# cansat.net
KiCad netlist of a schematic drawn in EAGLE
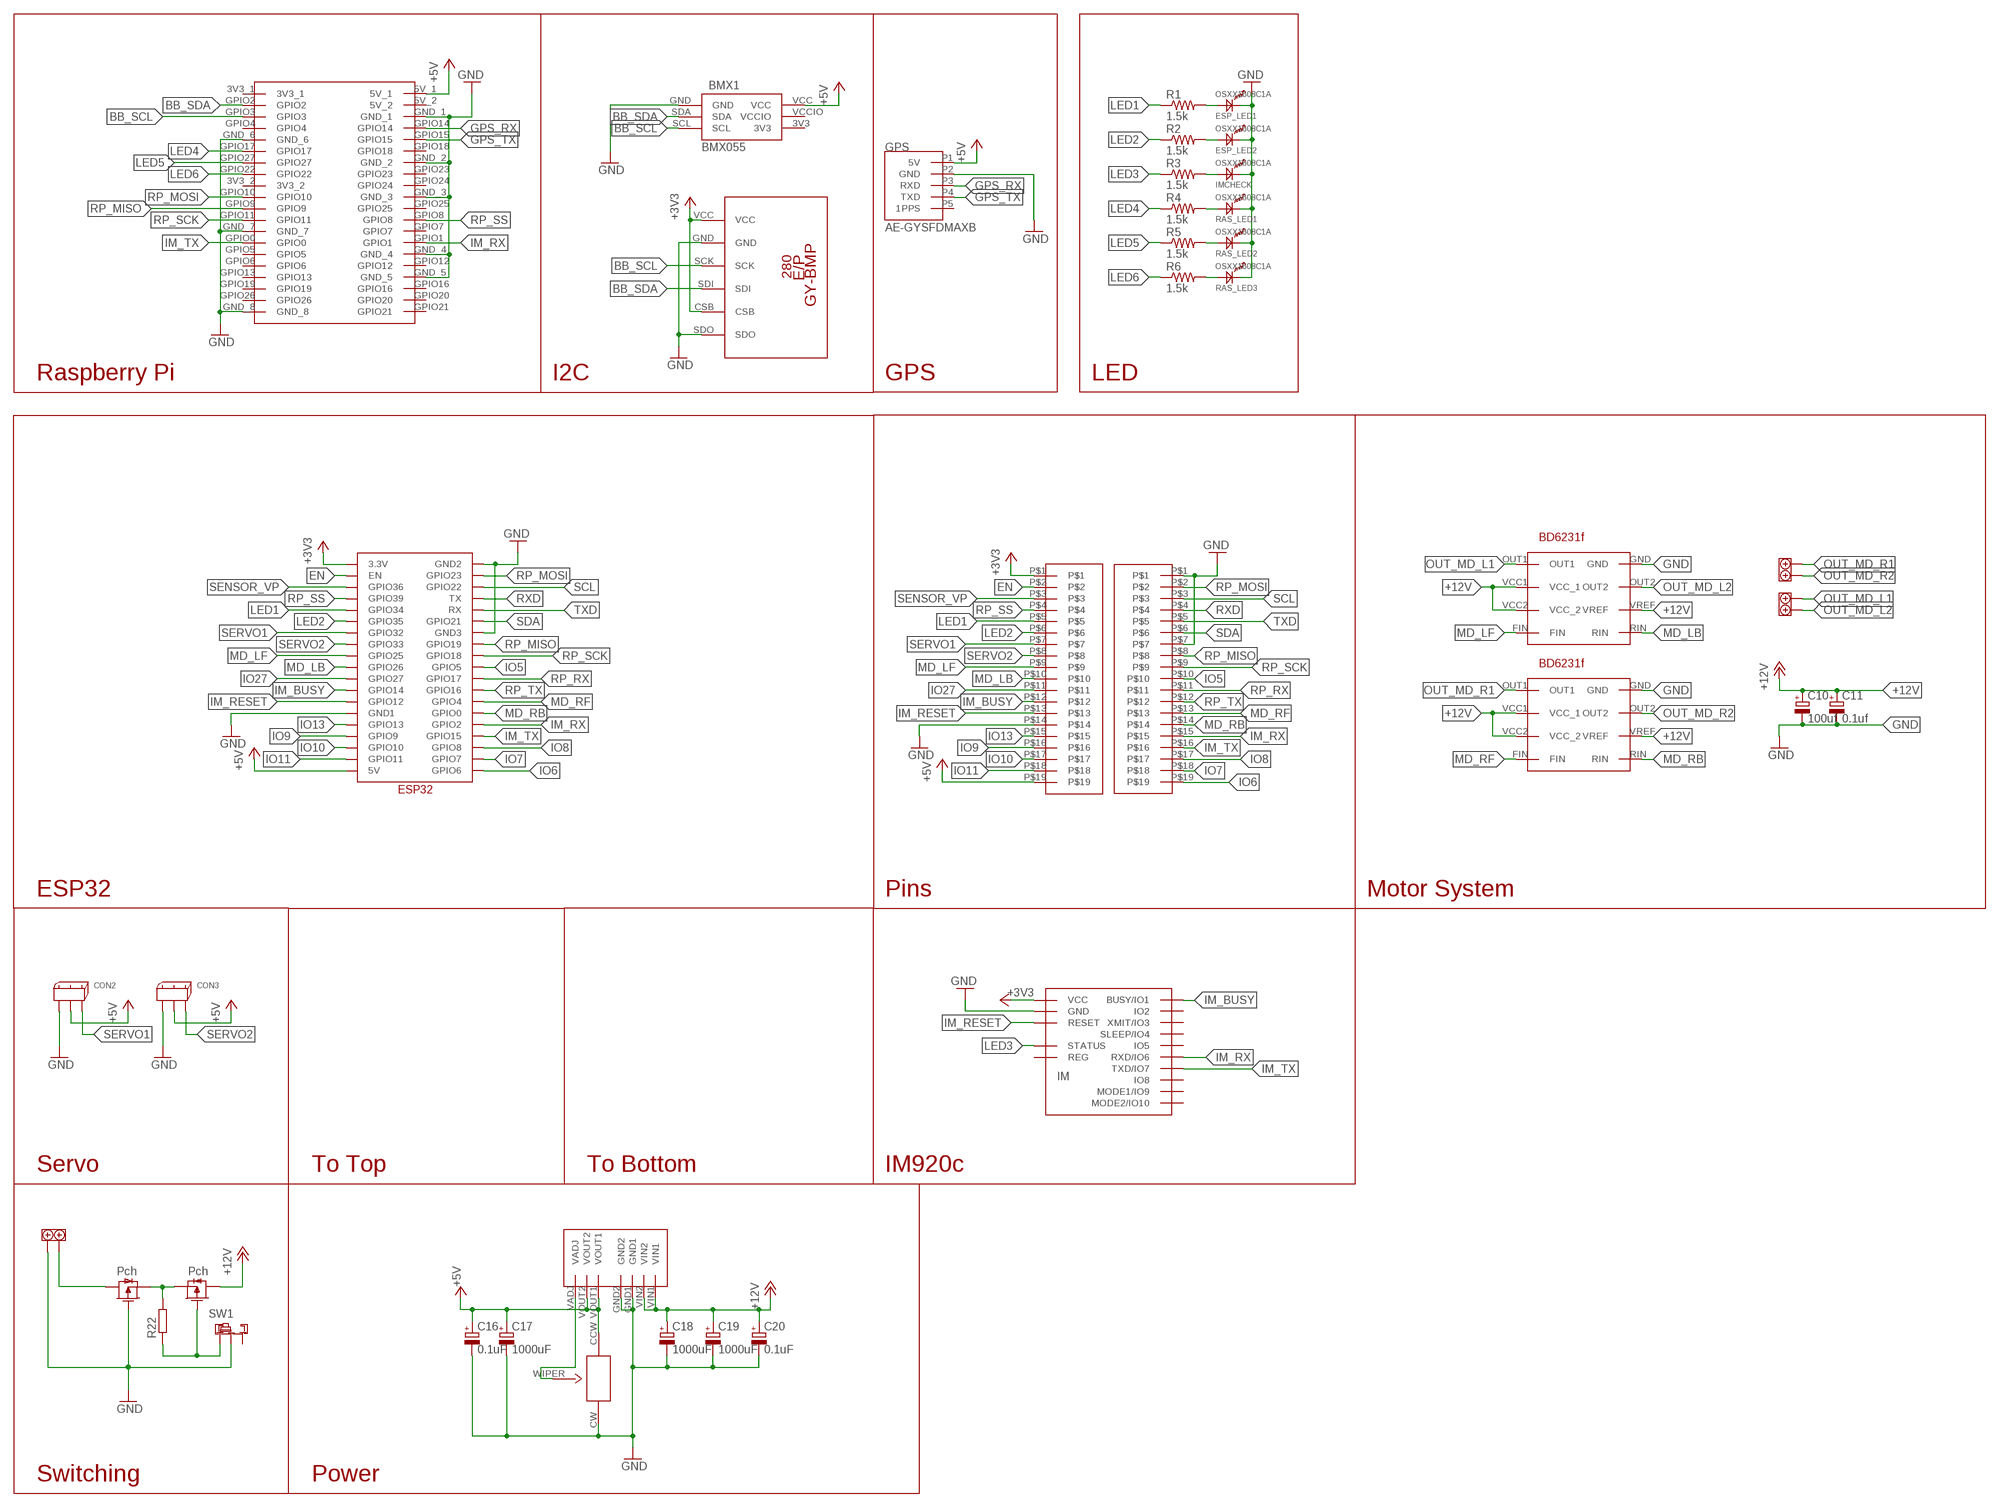
[diagram p0: schematic, sheet 1]

(export (version "E")
  (design (tool "Eeschema 10.0.6"))
  (components
    (comp (ref "100KR1")
      (value "100kR")
      (footprint "eagle-import:3362P")
      (libsource (lib "eagle-import") (part "3362P"))
    )
    (comp (ref "BMX1")
      (value "BMX055")
      (footprint "eagle-import:BMX055")
      (libsource (lib "eagle-import") (part "BMX055"))
    )
    (comp (ref "C10")
      (value "100uf")
      (footprint "eagle-import:E2,5-7")
      (libsource (lib "eagle-import") (part "CPOL-EUE2.5-7"))
    )
    (comp (ref "C11")
      (value "0.1uf")
      (footprint "eagle-import:E2,5-7")
      (libsource (lib "eagle-import") (part "CPOL-EUE2.5-7"))
    )
    (comp (ref "C16")
      (value "0.1uF")
      (footprint "eagle-import:E2,5-7")
      (libsource (lib "eagle-import") (part "CPOL-EUE2.5-7"))
    )
    (comp (ref "C17")
      (value "1000uF")
      (footprint "eagle-import:E5-10,5")
      (libsource (lib "eagle-import") (part "CPOL-EUE5-10.5"))
    )
    (comp (ref "C18")
      (value "1000uF")
      (footprint "eagle-import:E5-10,5")
      (libsource (lib "eagle-import") (part "CPOL-EUE5-10.5"))
    )
    (comp (ref "C19")
      (value "1000uF")
      (footprint "eagle-import:E5-10,5")
      (libsource (lib "eagle-import") (part "CPOL-EUE5-10.5"))
    )
    (comp (ref "C20")
      (value "0.1uF")
      (footprint "eagle-import:E2,5-7")
      (libsource (lib "eagle-import") (part "CPOL-EUE2.5-7"))
    )
    (comp (ref "CON2")
      (value "2.5_MINI-SPOX_3PIN")
      (footprint "eagle-import:2.5_MINI-SPOX_3PIN")
      (libsource (lib "eagle-import") (part "2.5_MINI-SPOX_3PIN"))
    )
    (comp (ref "CON3")
      (value "2.5_MINI-SPOX_3PIN")
      (footprint "eagle-import:2.5_MINI-SPOX_3PIN")
      (libsource (lib "eagle-import") (part "2.5_MINI-SPOX_3PIN"))
    )
    (comp (ref "ESP_LED1")
      (value "OSXX1608C1A")
      (footprint "eagle-import:OSXX1608C1A")
      (libsource (lib "eagle-import") (part "OSXX1608C1A"))
    )
    (comp (ref "ESP_LED2")
      (value "OSXX1608C1A")
      (footprint "eagle-import:OSXX1608C1A")
      (libsource (lib "eagle-import") (part "OSXX1608C1A"))
    )
    (comp (ref "GPS")
      (value "AE-GYSFDMAXB")
      (footprint "eagle-import:AE-GYSFDMAXB")
      (libsource (lib "eagle-import") (part "AE-GYSFDMAXB"))
    )
    (comp (ref "IM")
      (value "IM920C")
      (footprint "eagle-import:IM920C")
      (libsource (lib "eagle-import") (part "IM920C"))
    )
    (comp (ref "IMCHECK")
      (value "OSXX1608C1A")
      (footprint "eagle-import:OSXX1608C1A")
      (libsource (lib "eagle-import") (part "OSXX1608C1A"))
    )
    (comp (ref "MD_L")
      (value "BD6231F")
      (footprint "eagle-import:BD6231F")
      (libsource (lib "eagle-import") (part "BD6231F"))
    )
    (comp (ref "MD_R")
      (value "BD6231F")
      (footprint "eagle-import:BD6231F")
      (libsource (lib "eagle-import") (part "BD6231F"))
    )
    (comp (ref "PIN_L")
      (value "19_2.54")
      (footprint "eagle-import:19_2.54")
      (libsource (lib "eagle-import") (part "19_2.54"))
    )
    (comp (ref "PIN_R")
      (value "19_2.54")
      (footprint "eagle-import:19_2.54")
      (libsource (lib "eagle-import") (part "19_2.54"))
    )
    (comp (ref "R1")
      (value "1.5k")
      (footprint "eagle-import:R0603")
      (libsource (lib "eagle-import") (part "R-US_R0603"))
    )
    (comp (ref "R2")
      (value "1.5k")
      (footprint "eagle-import:R0603")
      (libsource (lib "eagle-import") (part "R-US_R0603"))
    )
    (comp (ref "R3")
      (value "1.5k")
      (footprint "eagle-import:R0603")
      (libsource (lib "eagle-import") (part "R-US_R0603"))
    )
    (comp (ref "R4")
      (value "1.5k")
      (footprint "eagle-import:R0603")
      (libsource (lib "eagle-import") (part "R-US_R0603"))
    )
    (comp (ref "R5")
      (value "1.5k")
      (footprint "eagle-import:R0603")
      (libsource (lib "eagle-import") (part "R-US_R0603"))
    )
    (comp (ref "R6")
      (value "1.5k")
      (footprint "eagle-import:R0603")
      (libsource (lib "eagle-import") (part "R-US_R0603"))
    )
    (comp (ref "R22")
      (value "R-EU_0207/10")
      (footprint "eagle-import:0207_10")
      (libsource (lib "eagle-import") (part "R-EU_0207/10"))
    )
    (comp (ref "RASPBERRYPI_4B")
      (value "RASPBERRYPI4B")
      (footprint "eagle-import:RASPBERRYPI4B")
      (libsource (lib "eagle-import") (part "RASPBERRYPI4B"))
    )
    (comp (ref "RAS_LED1")
      (value "OSXX1608C1A")
      (footprint "eagle-import:OSXX1608C1A")
      (libsource (lib "eagle-import") (part "OSXX1608C1A"))
    )
    (comp (ref "RAS_LED2")
      (value "OSXX1608C1A")
      (footprint "eagle-import:OSXX1608C1A")
      (libsource (lib "eagle-import") (part "OSXX1608C1A"))
    )
    (comp (ref "RAS_LED3")
      (value "OSXX1608C1A")
      (footprint "eagle-import:OSXX1608C1A")
      (libsource (lib "eagle-import") (part "OSXX1608C1A"))
    )
    (comp (ref "SW1")
      (value "SRIDE_SWITCH")
      (footprint "eagle-import:SRIDE_SWITCH")
      (libsource (lib "eagle-import") (part "SRIDE_SWITCH"))
    )
    (comp (ref "TM1")
      (value "TERMINAL_SLOPED_2PIN")
      (footprint "eagle-import:TERMINAL_SLOPED_2PIN")
      (libsource (lib "eagle-import") (part "TERMINAL_SLOPED_2PIN"))
    )
    (comp (ref "TM2")
      (value "TERMINAL_SLOPED_2PIN")
      (footprint "eagle-import:TERMINAL_SLOPED_2PIN")
      (libsource (lib "eagle-import") (part "TERMINAL_SLOPED_2PIN"))
    )
    (comp (ref "TM3")
      (value "TERMINAL_SLOPED_2PIN")
      (footprint "eagle-import:TERMINAL_SLOPED_2PIN")
      (libsource (lib "eagle-import") (part "TERMINAL_SLOPED_2PIN"))
    )
    (comp (ref "U$2")
      (value "ESP32")
      (footprint "eagle-import:ESP32")
      (libsource (lib "eagle-import") (part "ESP32"))
    )
    (comp (ref "U$7")
      (value "2SJ681-PCH")
      (footprint "eagle-import:2SJ681")
      (libsource (lib "eagle-import") (part "2SJ681-PCH"))
    )
    (comp (ref "U$8")
      (value "5V3A_KIC-053")
      (footprint "eagle-import:5V3A_KIC-053")
      (libsource (lib "eagle-import") (part "5V3A_KIC-053"))
    )
    (comp (ref "U$9")
      (value "GY-BPM280")
      (footprint "eagle-import:GY-BMP280-FOOTPRINT")
      (libsource (lib "eagle-import") (part "GY-BPM280"))
    )
    (comp (ref "U$10")
      (value "2SJ681-PCH")
      (footprint "eagle-import:2SJ681")
      (libsource (lib "eagle-import") (part "2SJ681-PCH"))
    )
  )
  (nets
    (net (code "1") (name "+3V3") (class "Default")
      (node (ref "IM") (pin "$P17") (pinfunction "VCC_$P17") (pintype "bidirectional"))
      (node (ref "PIN_L") (pin "P$1") (pinfunction "P$1_P$1") (pintype "bidirectional"))
      (node (ref "U$2") (pin "3.3V") (pinfunction "3.3V_3.3V") (pintype "bidirectional"))
      (node (ref "U$9") (pin "CSB") (pinfunction "CSB_CSB") (pintype "bidirectional"))
      (node (ref "U$9") (pin "VCC") (pinfunction "VCC_VCC") (pintype "bidirectional"))
    )
    (net (code "2") (name "+5V") (class "Default")
      (node (ref "100KR1") (pin "CCW") (pinfunction "CCW_CCW") (pintype "bidirectional"))
      (node (ref "BMX1") (pin "VCC") (pinfunction "VCC_VCC") (pintype "power_in"))
      (node (ref "C16") (pin "+") (pinfunction "+_+") (pintype "passive"))
      (node (ref "C17") (pin "+") (pinfunction "+_+") (pintype "passive"))
      (node (ref "CON2") (pin "2") (pinfunction "2_2") (pintype "bidirectional"))
      (node (ref "CON3") (pin "2") (pinfunction "2_2") (pintype "bidirectional"))
      (node (ref "GPS") (pin "P1") (pinfunction "5V_P1") (pintype "bidirectional"))
      (node (ref "PIN_L") (pin "P$19") (pinfunction "P$19_P$19") (pintype "bidirectional"))
      (node (ref "RASPBERRYPI_4B") (pin "5V_1") (pinfunction "5V_1_5V_1") (pintype "bidirectional"))
      (node (ref "U$2") (pin "5V") (pinfunction "5V_5V") (pintype "bidirectional"))
      (node (ref "U$8") (pin "VOUT1") (pinfunction "VOUT1_VOUT1") (pintype "bidirectional"))
      (node (ref "U$8") (pin "VOUT2") (pinfunction "VOUT2_VOUT2") (pintype "bidirectional"))
    )
    (net (code "3") (name "+12V") (class "Default")
      (node (ref "C10") (pin "+") (pinfunction "+_+") (pintype "passive"))
      (node (ref "C11") (pin "+") (pinfunction "+_+") (pintype "passive"))
      (node (ref "C18") (pin "+") (pinfunction "+_+") (pintype "passive"))
      (node (ref "C19") (pin "+") (pinfunction "+_+") (pintype "passive"))
      (node (ref "C20") (pin "+") (pinfunction "+_+") (pintype "passive"))
      (node (ref "MD_L") (pin "VCC1") (pinfunction "VCC_1_VCC1") (pintype "bidirectional"))
      (node (ref "MD_L") (pin "VCC2") (pinfunction "VCC_2_VCC2") (pintype "bidirectional"))
      (node (ref "MD_L") (pin "VREF") (pinfunction "VREF_VREF") (pintype "bidirectional"))
      (node (ref "MD_R") (pin "VCC1") (pinfunction "VCC_1_VCC1") (pintype "bidirectional"))
      (node (ref "MD_R") (pin "VCC2") (pinfunction "VCC_2_VCC2") (pintype "bidirectional"))
      (node (ref "MD_R") (pin "VREF") (pinfunction "VREF_VREF") (pintype "bidirectional"))
      (node (ref "U$10") (pin "DRAIN") (pinfunction "DRAIN_DRAIN") (pintype "bidirectional"))
      (node (ref "U$8") (pin "VIN1") (pinfunction "VIN1_VIN1") (pintype "bidirectional"))
      (node (ref "U$8") (pin "VIN2") (pinfunction "VIN2_VIN2") (pintype "bidirectional"))
    )
    (net (code "4") (name "/3V3") (class "Default")
      (node (ref "BMX1") (pin "3V3") (pinfunction "3V3_3V3") (pintype "power_in"))
    )
    (net (code "5") (name "/VCCIO") (class "Default")
      (node (ref "BMX1") (pin "VCCIO") (pinfunction "VCCIO_VCCIO") (pintype "power_in"))
    )
    (net (code "6") (name "BB_SCL") (class "Default")
      (node (ref "BMX1") (pin "SCL") (pinfunction "SCL_SCL") (pintype "bidirectional"))
      (node (ref "RASPBERRYPI_4B") (pin "GPIO3") (pinfunction "GPIO3_GPIO3") (pintype "bidirectional"))
      (node (ref "U$9") (pin "SCK") (pinfunction "SCK_SCK") (pintype "bidirectional"))
    )
    (net (code "7") (name "BB_SDA") (class "Default")
      (node (ref "BMX1") (pin "SDA") (pinfunction "SDA_SDA") (pintype "bidirectional"))
      (node (ref "RASPBERRYPI_4B") (pin "GPIO2") (pinfunction "GPIO2_GPIO2") (pintype "bidirectional"))
      (node (ref "U$9") (pin "SDI") (pinfunction "SDI_SDI") (pintype "bidirectional"))
    )
    (net (code "8") (name "EN") (class "Default")
      (node (ref "PIN_L") (pin "P$2") (pinfunction "P$2_P$2") (pintype "bidirectional"))
      (node (ref "U$2") (pin "EN") (pinfunction "EN_EN") (pintype "bidirectional"))
    )
    (net (code "9") (name "GND") (class "Default")
      (node (ref "100KR1") (pin "CW") (pinfunction "CW_CW") (pintype "bidirectional"))
      (node (ref "BMX1") (pin "GND") (pinfunction "GND_GND") (pintype "power_in"))
      (node (ref "C10") (pin "-") (pinfunction "-_-") (pintype "passive"))
      (node (ref "C11") (pin "-") (pinfunction "-_-") (pintype "passive"))
      (node (ref "C16") (pin "-") (pinfunction "-_-") (pintype "passive"))
      (node (ref "C17") (pin "-") (pinfunction "-_-") (pintype "passive"))
      (node (ref "C18") (pin "-") (pinfunction "-_-") (pintype "passive"))
      (node (ref "C19") (pin "-") (pinfunction "-_-") (pintype "passive"))
      (node (ref "C20") (pin "-") (pinfunction "-_-") (pintype "passive"))
      (node (ref "CON2") (pin "1") (pinfunction "1_1") (pintype "bidirectional"))
      (node (ref "CON3") (pin "1") (pinfunction "1_1") (pintype "bidirectional"))
      (node (ref "ESP_LED1") (pin "CT") (pinfunction "CT_CT") (pintype "bidirectional"))
      (node (ref "ESP_LED2") (pin "CT") (pinfunction "CT_CT") (pintype "bidirectional"))
      (node (ref "GPS") (pin "P2") (pinfunction "GND_P2") (pintype "bidirectional"))
      (node (ref "IM") (pin "$P18") (pinfunction "GND_$P18") (pintype "bidirectional"))
      (node (ref "IMCHECK") (pin "CT") (pinfunction "CT_CT") (pintype "bidirectional"))
      (node (ref "MD_L") (pin "GND") (pinfunction "GND_GND") (pintype "bidirectional"))
      (node (ref "MD_R") (pin "GND") (pinfunction "GND_GND") (pintype "bidirectional"))
      (node (ref "PIN_L") (pin "P$14") (pinfunction "P$14_P$14") (pintype "bidirectional"))
      (node (ref "PIN_R") (pin "P$1") (pinfunction "P$1_P$1") (pintype "bidirectional"))
      (node (ref "PIN_R") (pin "P$7") (pinfunction "P$7_P$7") (pintype "bidirectional"))
      (node (ref "RASPBERRYPI_4B") (pin "GND_1") (pinfunction "GND_1_GND_1") (pintype "bidirectional"))
      (node (ref "RASPBERRYPI_4B") (pin "GND_2") (pinfunction "GND_2_GND_2") (pintype "bidirectional"))
      (node (ref "RASPBERRYPI_4B") (pin "GND_3") (pinfunction "GND_3_GND_3") (pintype "bidirectional"))
      (node (ref "RASPBERRYPI_4B") (pin "GND_4") (pinfunction "GND_4_GND_4") (pintype "bidirectional"))
      (node (ref "RASPBERRYPI_4B") (pin "GND_5") (pinfunction "GND_5_GND_5") (pintype "bidirectional"))
      (node (ref "RASPBERRYPI_4B") (pin "GND_6") (pinfunction "GND_6_GND_6") (pintype "bidirectional"))
      (node (ref "RASPBERRYPI_4B") (pin "GND_7") (pinfunction "GND_7_GND_7") (pintype "bidirectional"))
      (node (ref "RASPBERRYPI_4B") (pin "GND_8") (pinfunction "GND_8_GND_8") (pintype "bidirectional"))
      (node (ref "RAS_LED1") (pin "CT") (pinfunction "CT_CT") (pintype "bidirectional"))
      (node (ref "RAS_LED2") (pin "CT") (pinfunction "CT_CT") (pintype "bidirectional"))
      (node (ref "RAS_LED3") (pin "CT") (pinfunction "CT_CT") (pintype "bidirectional"))
      (node (ref "SW1") (pin "LR") (pinfunction "LR_LR") (pintype "bidirectional"))
      (node (ref "TM3") (pin "2") (pinfunction "2_2") (pintype "bidirectional"))
      (node (ref "U$2") (pin "GND1") (pinfunction "GND1_GND1") (pintype "bidirectional"))
      (node (ref "U$2") (pin "GND2") (pinfunction "GND2_GND2") (pintype "bidirectional"))
      (node (ref "U$2") (pin "GND3") (pinfunction "GND3_GND3") (pintype "bidirectional"))
      (node (ref "U$7") (pin "GATE") (pinfunction "GATE_GATE") (pintype "bidirectional"))
      (node (ref "U$8") (pin "GND1") (pinfunction "GND1_GND1") (pintype "bidirectional"))
      (node (ref "U$8") (pin "GND2") (pinfunction "GND2_GND2") (pintype "bidirectional"))
      (node (ref "U$9") (pin "GND") (pinfunction "GND_GND") (pintype "bidirectional"))
      (node (ref "U$9") (pin "SDO") (pinfunction "SDO_SDO") (pintype "bidirectional"))
    )
    (net (code "10") (name "GPS_RX") (class "Default")
      (node (ref "GPS") (pin "P3") (pinfunction "RXD_P3") (pintype "bidirectional"))
      (node (ref "RASPBERRYPI_4B") (pin "GPIO14") (pinfunction "GPIO14_GPIO14") (pintype "bidirectional"))
    )
    (net (code "11") (name "GPS_TX") (class "Default")
      (node (ref "GPS") (pin "P4") (pinfunction "TXD_P4") (pintype "bidirectional"))
      (node (ref "RASPBERRYPI_4B") (pin "GPIO15") (pinfunction "GPIO15_GPIO15") (pintype "bidirectional"))
    )
    (net (code "12") (name "IM_BUSY") (class "Default")
      (node (ref "IM") (pin "$P1") (pinfunction "BUSY/IO1_$P1") (pintype "bidirectional"))
      (node (ref "PIN_L") (pin "P$12") (pinfunction "P$12_P$12") (pintype "bidirectional"))
      (node (ref "U$2") (pin "GPIO14") (pinfunction "GPIO14_GPIO14") (pintype "bidirectional"))
    )
    (net (code "13") (name "IM_RESET") (class "Default")
      (node (ref "IM") (pin "$P19") (pinfunction "RESET_$P19") (pintype "bidirectional"))
      (node (ref "PIN_L") (pin "P$13") (pinfunction "P$13_P$13") (pintype "bidirectional"))
      (node (ref "U$2") (pin "GPIO12") (pinfunction "GPIO12_GPIO12") (pintype "bidirectional"))
    )
    (net (code "14") (name "IM_RX") (class "Default")
      (node (ref "IM") (pin "$P6") (pinfunction "RXD/IO6_$P6") (pintype "bidirectional"))
      (node (ref "PIN_R") (pin "P$15") (pinfunction "P$15_P$15") (pintype "bidirectional"))
      (node (ref "RASPBERRYPI_4B") (pin "GPIO1") (pinfunction "GPIO1_GPIO1") (pintype "bidirectional"))
      (node (ref "U$2") (pin "GPIO2") (pinfunction "GPIO2_GPIO2") (pintype "bidirectional"))
    )
    (net (code "15") (name "IM_TX") (class "Default")
      (node (ref "IM") (pin "$P7") (pinfunction "TXD/IO7_$P7") (pintype "bidirectional"))
      (node (ref "PIN_R") (pin "P$16") (pinfunction "P$16_P$16") (pintype "bidirectional"))
      (node (ref "RASPBERRYPI_4B") (pin "GPIO0") (pinfunction "GPIO0_GPIO0") (pintype "bidirectional"))
      (node (ref "U$2") (pin "GPIO15") (pinfunction "GPIO15_GPIO15") (pintype "bidirectional"))
    )
    (net (code "16") (name "IO5") (class "Default")
      (node (ref "PIN_R") (pin "P$10") (pinfunction "P$10_P$10") (pintype "bidirectional"))
      (node (ref "U$2") (pin "GPIO5") (pinfunction "GPIO5_GPIO5") (pintype "bidirectional"))
    )
    (net (code "17") (name "IO6") (class "Default")
      (node (ref "PIN_R") (pin "P$19") (pinfunction "P$19_P$19") (pintype "bidirectional"))
      (node (ref "U$2") (pin "GPIO6") (pinfunction "GPIO6_GPIO6") (pintype "bidirectional"))
    )
    (net (code "18") (name "IO7") (class "Default")
      (node (ref "PIN_R") (pin "P$18") (pinfunction "P$18_P$18") (pintype "bidirectional"))
      (node (ref "U$2") (pin "GPIO7") (pinfunction "GPIO7_GPIO7") (pintype "bidirectional"))
    )
    (net (code "19") (name "IO8") (class "Default")
      (node (ref "PIN_R") (pin "P$17") (pinfunction "P$17_P$17") (pintype "bidirectional"))
      (node (ref "U$2") (pin "GPIO8") (pinfunction "GPIO8_GPIO8") (pintype "bidirectional"))
    )
    (net (code "20") (name "IO9") (class "Default")
      (node (ref "PIN_L") (pin "P$16") (pinfunction "P$16_P$16") (pintype "bidirectional"))
      (node (ref "U$2") (pin "GPIO9") (pinfunction "GPIO9_GPIO9") (pintype "bidirectional"))
    )
    (net (code "21") (name "IO10") (class "Default")
      (node (ref "PIN_L") (pin "P$17") (pinfunction "P$17_P$17") (pintype "bidirectional"))
      (node (ref "U$2") (pin "GPIO10") (pinfunction "GPIO10_GPIO10") (pintype "bidirectional"))
    )
    (net (code "22") (name "IO11") (class "Default")
      (node (ref "PIN_L") (pin "P$18") (pinfunction "P$18_P$18") (pintype "bidirectional"))
      (node (ref "U$2") (pin "GPIO11") (pinfunction "GPIO11_GPIO11") (pintype "bidirectional"))
    )
    (net (code "23") (name "IO13") (class "Default")
      (node (ref "PIN_L") (pin "P$15") (pinfunction "P$15_P$15") (pintype "bidirectional"))
      (node (ref "U$2") (pin "GPIO13") (pinfunction "GPIO13_GPIO13") (pintype "bidirectional"))
    )
    (net (code "24") (name "IO27") (class "Default")
      (node (ref "PIN_L") (pin "P$11") (pinfunction "P$11_P$11") (pintype "bidirectional"))
      (node (ref "U$2") (pin "GPIO27") (pinfunction "GPIO27_GPIO27") (pintype "bidirectional"))
    )
    (net (code "25") (name "LED1") (class "Default")
      (node (ref "PIN_L") (pin "P$5") (pinfunction "P$5_P$5") (pintype "bidirectional"))
      (node (ref "R1") (pin "1") (pinfunction "1_1") (pintype "passive"))
      (node (ref "U$2") (pin "GPIO34") (pinfunction "GPIO34_GPIO34") (pintype "bidirectional"))
    )
    (net (code "26") (name "LED2") (class "Default")
      (node (ref "PIN_L") (pin "P$6") (pinfunction "P$6_P$6") (pintype "bidirectional"))
      (node (ref "R2") (pin "1") (pinfunction "1_1") (pintype "passive"))
      (node (ref "U$2") (pin "GPIO35") (pinfunction "GPIO35_GPIO35") (pintype "bidirectional"))
    )
    (net (code "27") (name "LED3") (class "Default")
      (node (ref "IM") (pin "$P15") (pinfunction "STATUS_$P15") (pintype "bidirectional"))
      (node (ref "R3") (pin "1") (pinfunction "1_1") (pintype "passive"))
    )
    (net (code "28") (name "LED4") (class "Default")
      (node (ref "R4") (pin "1") (pinfunction "1_1") (pintype "passive"))
      (node (ref "RASPBERRYPI_4B") (pin "GPIO17") (pinfunction "GPIO17_GPIO17") (pintype "bidirectional"))
    )
    (net (code "29") (name "LED5") (class "Default")
      (node (ref "R5") (pin "1") (pinfunction "1_1") (pintype "passive"))
      (node (ref "RASPBERRYPI_4B") (pin "GPIO27") (pinfunction "GPIO27_GPIO27") (pintype "bidirectional"))
    )
    (net (code "30") (name "LED6") (class "Default")
      (node (ref "R6") (pin "1") (pinfunction "1_1") (pintype "passive"))
      (node (ref "RASPBERRYPI_4B") (pin "GPIO22") (pinfunction "GPIO22_GPIO22") (pintype "bidirectional"))
    )
    (net (code "31") (name "MD_LB") (class "Default")
      (node (ref "MD_L") (pin "RIN") (pinfunction "RIN_RIN") (pintype "bidirectional"))
      (node (ref "PIN_L") (pin "P$10") (pinfunction "P$10_P$10") (pintype "bidirectional"))
      (node (ref "U$2") (pin "GPIO26") (pinfunction "GPIO26_GPIO26") (pintype "bidirectional"))
    )
    (net (code "32") (name "MD_LF") (class "Default")
      (node (ref "MD_L") (pin "FIN") (pinfunction "FIN_FIN") (pintype "bidirectional"))
      (node (ref "PIN_L") (pin "P$9") (pinfunction "P$9_P$9") (pintype "bidirectional"))
      (node (ref "U$2") (pin "GPIO25") (pinfunction "GPIO25_GPIO25") (pintype "bidirectional"))
    )
    (net (code "33") (name "MD_RB") (class "Default")
      (node (ref "MD_R") (pin "RIN") (pinfunction "RIN_RIN") (pintype "bidirectional"))
      (node (ref "PIN_R") (pin "P$14") (pinfunction "P$14_P$14") (pintype "bidirectional"))
      (node (ref "U$2") (pin "GPIO0") (pinfunction "GPIO0_GPIO0") (pintype "bidirectional"))
    )
    (net (code "34") (name "MD_RF") (class "Default")
      (node (ref "MD_R") (pin "FIN") (pinfunction "FIN_FIN") (pintype "bidirectional"))
      (node (ref "PIN_R") (pin "P$13") (pinfunction "P$13_P$13") (pintype "bidirectional"))
      (node (ref "U$2") (pin "GPIO4") (pinfunction "GPIO4_GPIO4") (pintype "bidirectional"))
    )
    (net (code "35") (name "Net-(100KR1-PadWIPER)") (class "Default")
      (node (ref "100KR1") (pin "WIPER") (pinfunction "WIPER_WIPER") (pintype "bidirectional"))
      (node (ref "U$8") (pin "VADJ") (pinfunction "VADJ_VADJ") (pintype "bidirectional"))
    )
    (net (code "36") (name "Net-(ESP_LED1-PadAN)") (class "Default")
      (node (ref "ESP_LED1") (pin "AN") (pinfunction "AN_AN") (pintype "bidirectional"))
      (node (ref "R1") (pin "2") (pinfunction "2_2") (pintype "passive"))
    )
    (net (code "37") (name "Net-(ESP_LED2-PadAN)") (class "Default")
      (node (ref "ESP_LED2") (pin "AN") (pinfunction "AN_AN") (pintype "bidirectional"))
      (node (ref "R2") (pin "2") (pinfunction "2_2") (pintype "passive"))
    )
    (net (code "38") (name "Net-(IMCHECK-PadAN)") (class "Default")
      (node (ref "IMCHECK") (pin "AN") (pinfunction "AN_AN") (pintype "bidirectional"))
      (node (ref "R3") (pin "2") (pinfunction "2_2") (pintype "passive"))
    )
    (net (code "39") (name "Net-(R4-Pad2)") (class "Default")
      (node (ref "R4") (pin "2") (pinfunction "2_2") (pintype "passive"))
      (node (ref "RAS_LED1") (pin "AN") (pinfunction "AN_AN") (pintype "bidirectional"))
    )
    (net (code "40") (name "Net-(R5-Pad2)") (class "Default")
      (node (ref "R5") (pin "2") (pinfunction "2_2") (pintype "passive"))
      (node (ref "RAS_LED2") (pin "AN") (pinfunction "AN_AN") (pintype "bidirectional"))
    )
    (net (code "41") (name "Net-(R6-Pad2)") (class "Default")
      (node (ref "R6") (pin "2") (pinfunction "2_2") (pintype "passive"))
      (node (ref "RAS_LED3") (pin "AN") (pinfunction "AN_AN") (pintype "bidirectional"))
    )
    (net (code "42") (name "Net-(R22-Pad1)") (class "Default")
      (node (ref "R22") (pin "1") (pinfunction "1_1") (pintype "passive"))
      (node (ref "SW1") (pin "L") (pinfunction "L_L") (pintype "bidirectional"))
      (node (ref "U$10") (pin "GATE") (pinfunction "GATE_GATE") (pintype "bidirectional"))
    )
    (net (code "43") (name "Net-(R22-Pad2)") (class "Default")
      (node (ref "R22") (pin "2") (pinfunction "2_2") (pintype "passive"))
      (node (ref "U$10") (pin "SOURCE") (pinfunction "SOURCE_SOURCE") (pintype "bidirectional"))
      (node (ref "U$7") (pin "SOURCE") (pinfunction "SOURCE_SOURCE") (pintype "bidirectional"))
    )
    (net (code "44") (name "Net-(TM3-Pad1)") (class "Default")
      (node (ref "TM3") (pin "1") (pinfunction "1_1") (pintype "bidirectional"))
      (node (ref "U$7") (pin "DRAIN") (pinfunction "DRAIN_DRAIN") (pintype "bidirectional"))
    )
    (net (code "45") (name "OUT_MD_L1") (class "Default")
      (node (ref "MD_L") (pin "OUT1") (pinfunction "OUT1_OUT1") (pintype "bidirectional"))
      (node (ref "TM2") (pin "1") (pinfunction "1_1") (pintype "bidirectional"))
    )
    (net (code "46") (name "OUT_MD_L2") (class "Default")
      (node (ref "MD_L") (pin "OUT2") (pinfunction "OUT2_OUT2") (pintype "bidirectional"))
      (node (ref "TM2") (pin "2") (pinfunction "2_2") (pintype "bidirectional"))
    )
    (net (code "47") (name "OUT_MD_R1") (class "Default")
      (node (ref "MD_R") (pin "OUT1") (pinfunction "OUT1_OUT1") (pintype "bidirectional"))
      (node (ref "TM1") (pin "1") (pinfunction "1_1") (pintype "bidirectional"))
    )
    (net (code "48") (name "OUT_MD_R2") (class "Default")
      (node (ref "MD_R") (pin "OUT2") (pinfunction "OUT2_OUT2") (pintype "bidirectional"))
      (node (ref "TM1") (pin "2") (pinfunction "2_2") (pintype "bidirectional"))
    )
    (net (code "49") (name "RP_MISO") (class "Default")
      (node (ref "PIN_R") (pin "P$8") (pinfunction "P$8_P$8") (pintype "bidirectional"))
      (node (ref "RASPBERRYPI_4B") (pin "GPIO9") (pinfunction "GPIO9_GPIO9") (pintype "bidirectional"))
      (node (ref "U$2") (pin "GPIO19") (pinfunction "GPIO19_GPIO19") (pintype "bidirectional"))
    )
    (net (code "50") (name "RP_MOSI") (class "Default")
      (node (ref "PIN_R") (pin "P$2") (pinfunction "P$2_P$2") (pintype "bidirectional"))
      (node (ref "RASPBERRYPI_4B") (pin "GPIO10") (pinfunction "GPIO10_GPIO10") (pintype "bidirectional"))
      (node (ref "U$2") (pin "GPIO23") (pinfunction "GPIO23_GPIO23") (pintype "bidirectional"))
    )
    (net (code "51") (name "RP_RX") (class "Default")
      (node (ref "PIN_R") (pin "P$11") (pinfunction "P$11_P$11") (pintype "bidirectional"))
      (node (ref "U$2") (pin "GPIO17") (pinfunction "GPIO17_GPIO17") (pintype "bidirectional"))
    )
    (net (code "52") (name "RP_SCK") (class "Default")
      (node (ref "PIN_R") (pin "P$9") (pinfunction "P$9_P$9") (pintype "bidirectional"))
      (node (ref "RASPBERRYPI_4B") (pin "GPIO11") (pinfunction "GPIO11_GPIO11") (pintype "bidirectional"))
      (node (ref "U$2") (pin "GPIO18") (pinfunction "GPIO18_GPIO18") (pintype "bidirectional"))
    )
    (net (code "53") (name "RP_SS") (class "Default")
      (node (ref "PIN_L") (pin "P$4") (pinfunction "P$4_P$4") (pintype "bidirectional"))
      (node (ref "RASPBERRYPI_4B") (pin "GPIO8") (pinfunction "GPIO8_GPIO8") (pintype "bidirectional"))
      (node (ref "U$2") (pin "GPIO39") (pinfunction "GPIO39_GPIO39") (pintype "bidirectional"))
    )
    (net (code "54") (name "RP_TX") (class "Default")
      (node (ref "PIN_R") (pin "P$12") (pinfunction "P$12_P$12") (pintype "bidirectional"))
      (node (ref "U$2") (pin "GPIO16") (pinfunction "GPIO16_GPIO16") (pintype "bidirectional"))
    )
    (net (code "55") (name "RXD") (class "Default")
      (node (ref "PIN_R") (pin "P$4") (pinfunction "P$4_P$4") (pintype "bidirectional"))
      (node (ref "U$2") (pin "TX") (pinfunction "TX_TX") (pintype "bidirectional"))
    )
    (net (code "56") (name "SCL") (class "Default")
      (node (ref "PIN_R") (pin "P$3") (pinfunction "P$3_P$3") (pintype "bidirectional"))
      (node (ref "U$2") (pin "GPIO22") (pinfunction "GPIO22_GPIO22") (pintype "bidirectional"))
    )
    (net (code "57") (name "SDA") (class "Default")
      (node (ref "PIN_R") (pin "P$6") (pinfunction "P$6_P$6") (pintype "bidirectional"))
      (node (ref "U$2") (pin "GPIO21") (pinfunction "GPIO21_GPIO21") (pintype "bidirectional"))
    )
    (net (code "58") (name "SENSOR_VP") (class "Default")
      (node (ref "PIN_L") (pin "P$3") (pinfunction "P$3_P$3") (pintype "bidirectional"))
      (node (ref "U$2") (pin "GPIO36") (pinfunction "GPIO36_GPIO36") (pintype "bidirectional"))
    )
    (net (code "59") (name "SERVO1") (class "Default")
      (node (ref "CON2") (pin "3") (pinfunction "3_3") (pintype "bidirectional"))
      (node (ref "PIN_L") (pin "P$7") (pinfunction "P$7_P$7") (pintype "bidirectional"))
      (node (ref "U$2") (pin "GPIO32") (pinfunction "GPIO32_GPIO32") (pintype "bidirectional"))
    )
    (net (code "60") (name "SERVO2") (class "Default")
      (node (ref "CON3") (pin "3") (pinfunction "3_3") (pintype "bidirectional"))
      (node (ref "PIN_L") (pin "P$8") (pinfunction "P$8_P$8") (pintype "bidirectional"))
      (node (ref "U$2") (pin "GPIO33") (pinfunction "GPIO33_GPIO33") (pintype "bidirectional"))
    )
    (net (code "61") (name "TXD") (class "Default")
      (node (ref "PIN_R") (pin "P$5") (pinfunction "P$5_P$5") (pintype "bidirectional"))
      (node (ref "U$2") (pin "RX") (pinfunction "RX_RX") (pintype "bidirectional"))
    )
    (net (code "62") (name "unconnected-(GPS-1PPS-PadP5)") (class "Default")
      (node (ref "GPS") (pin "P5") (pinfunction "1PPS_P5") (pintype "bidirectional"))
    )
    (net (code "63") (name "unconnected-(IM-IO2-Pad$P2)") (class "Default")
      (node (ref "IM") (pin "$P2") (pinfunction "IO2_$P2") (pintype "bidirectional"))
    )
    (net (code "64") (name "unconnected-(IM-IO5-Pad$P5)") (class "Default")
      (node (ref "IM") (pin "$P5") (pinfunction "IO5_$P5") (pintype "bidirectional"))
    )
    (net (code "65") (name "unconnected-(IM-IO8-Pad$P8)") (class "Default")
      (node (ref "IM") (pin "$P8") (pinfunction "IO8_$P8") (pintype "bidirectional"))
    )
    (net (code "66") (name "unconnected-(IM-MODE1{slash}IO9-Pad$P9)") (class "Default")
      (node (ref "IM") (pin "$P9") (pinfunction "MODE1/IO9_$P9") (pintype "bidirectional"))
    )
    (net (code "67") (name "unconnected-(IM-MODE2{slash}IO10-Pad$P10)") (class "Default")
      (node (ref "IM") (pin "$P10") (pinfunction "MODE2/IO10_$P10") (pintype "bidirectional"))
    )
    (net (code "68") (name "unconnected-(IM-REG-Pad$P16)") (class "Default")
      (node (ref "IM") (pin "$P16") (pinfunction "REG_$P16") (pintype "bidirectional"))
    )
    (net (code "69") (name "unconnected-(IM-SLEEP{slash}IO4-Pad$P4)") (class "Default")
      (node (ref "IM") (pin "$P4") (pinfunction "SLEEP/IO4_$P4") (pintype "bidirectional"))
    )
    (net (code "70") (name "unconnected-(IM-XMIT{slash}IO3-Pad$P3)") (class "Default")
      (node (ref "IM") (pin "$P3") (pinfunction "XMIT/IO3_$P3") (pintype "bidirectional"))
    )
    (net (code "71") (name "unconnected-(RASPBERRYPI_4B-Pad3V3_1)") (class "Default")
      (node (ref "RASPBERRYPI_4B") (pin "3V3_1") (pinfunction "3V3_1_3V3_1") (pintype "bidirectional"))
    )
    (net (code "72") (name "unconnected-(RASPBERRYPI_4B-Pad3V3_2)") (class "Default")
      (node (ref "RASPBERRYPI_4B") (pin "3V3_2") (pinfunction "3V3_2_3V3_2") (pintype "bidirectional"))
    )
    (net (code "73") (name "unconnected-(RASPBERRYPI_4B-Pad5V_2)") (class "Default")
      (node (ref "RASPBERRYPI_4B") (pin "5V_2") (pinfunction "5V_2_5V_2") (pintype "bidirectional"))
    )
    (net (code "74") (name "unconnected-(RASPBERRYPI_4B-PadGPIO4)") (class "Default")
      (node (ref "RASPBERRYPI_4B") (pin "GPIO4") (pinfunction "GPIO4_GPIO4") (pintype "bidirectional"))
    )
    (net (code "75") (name "unconnected-(RASPBERRYPI_4B-PadGPIO5)") (class "Default")
      (node (ref "RASPBERRYPI_4B") (pin "GPIO5") (pinfunction "GPIO5_GPIO5") (pintype "bidirectional"))
    )
    (net (code "76") (name "unconnected-(RASPBERRYPI_4B-PadGPIO6)") (class "Default")
      (node (ref "RASPBERRYPI_4B") (pin "GPIO6") (pinfunction "GPIO6_GPIO6") (pintype "bidirectional"))
    )
    (net (code "77") (name "unconnected-(RASPBERRYPI_4B-PadGPIO7)") (class "Default")
      (node (ref "RASPBERRYPI_4B") (pin "GPIO7") (pinfunction "GPIO7_GPIO7") (pintype "bidirectional"))
    )
    (net (code "78") (name "unconnected-(RASPBERRYPI_4B-PadGPIO12)") (class "Default")
      (node (ref "RASPBERRYPI_4B") (pin "GPIO12") (pinfunction "GPIO12_GPIO12") (pintype "bidirectional"))
    )
    (net (code "79") (name "unconnected-(RASPBERRYPI_4B-PadGPIO13)") (class "Default")
      (node (ref "RASPBERRYPI_4B") (pin "GPIO13") (pinfunction "GPIO13_GPIO13") (pintype "bidirectional"))
    )
    (net (code "80") (name "unconnected-(RASPBERRYPI_4B-PadGPIO16)") (class "Default")
      (node (ref "RASPBERRYPI_4B") (pin "GPIO16") (pinfunction "GPIO16_GPIO16") (pintype "bidirectional"))
    )
    (net (code "81") (name "unconnected-(RASPBERRYPI_4B-PadGPIO18)") (class "Default")
      (node (ref "RASPBERRYPI_4B") (pin "GPIO18") (pinfunction "GPIO18_GPIO18") (pintype "bidirectional"))
    )
    (net (code "82") (name "unconnected-(RASPBERRYPI_4B-PadGPIO19)") (class "Default")
      (node (ref "RASPBERRYPI_4B") (pin "GPIO19") (pinfunction "GPIO19_GPIO19") (pintype "bidirectional"))
    )
    (net (code "83") (name "unconnected-(RASPBERRYPI_4B-PadGPIO20)") (class "Default")
      (node (ref "RASPBERRYPI_4B") (pin "GPIO20") (pinfunction "GPIO20_GPIO20") (pintype "bidirectional"))
    )
    (net (code "84") (name "unconnected-(RASPBERRYPI_4B-PadGPIO21)") (class "Default")
      (node (ref "RASPBERRYPI_4B") (pin "GPIO21") (pinfunction "GPIO21_GPIO21") (pintype "bidirectional"))
    )
    (net (code "85") (name "unconnected-(RASPBERRYPI_4B-PadGPIO23)") (class "Default")
      (node (ref "RASPBERRYPI_4B") (pin "GPIO23") (pinfunction "GPIO23_GPIO23") (pintype "bidirectional"))
    )
    (net (code "86") (name "unconnected-(RASPBERRYPI_4B-PadGPIO24)") (class "Default")
      (node (ref "RASPBERRYPI_4B") (pin "GPIO24") (pinfunction "GPIO24_GPIO24") (pintype "bidirectional"))
    )
    (net (code "87") (name "unconnected-(RASPBERRYPI_4B-PadGPIO25)") (class "Default")
      (node (ref "RASPBERRYPI_4B") (pin "GPIO25") (pinfunction "GPIO25_GPIO25") (pintype "bidirectional"))
    )
    (net (code "88") (name "unconnected-(RASPBERRYPI_4B-PadGPIO26)") (class "Default")
      (node (ref "RASPBERRYPI_4B") (pin "GPIO26") (pinfunction "GPIO26_GPIO26") (pintype "bidirectional"))
    )
    (net (code "89") (name "unconnected-(SW1-PadR)") (class "Default")
      (node (ref "SW1") (pin "R") (pinfunction "R_R") (pintype "bidirectional"))
    )
  )
)
